# telescope_circuit.net
KiCad netlist of a schematic drawn in EAGLE
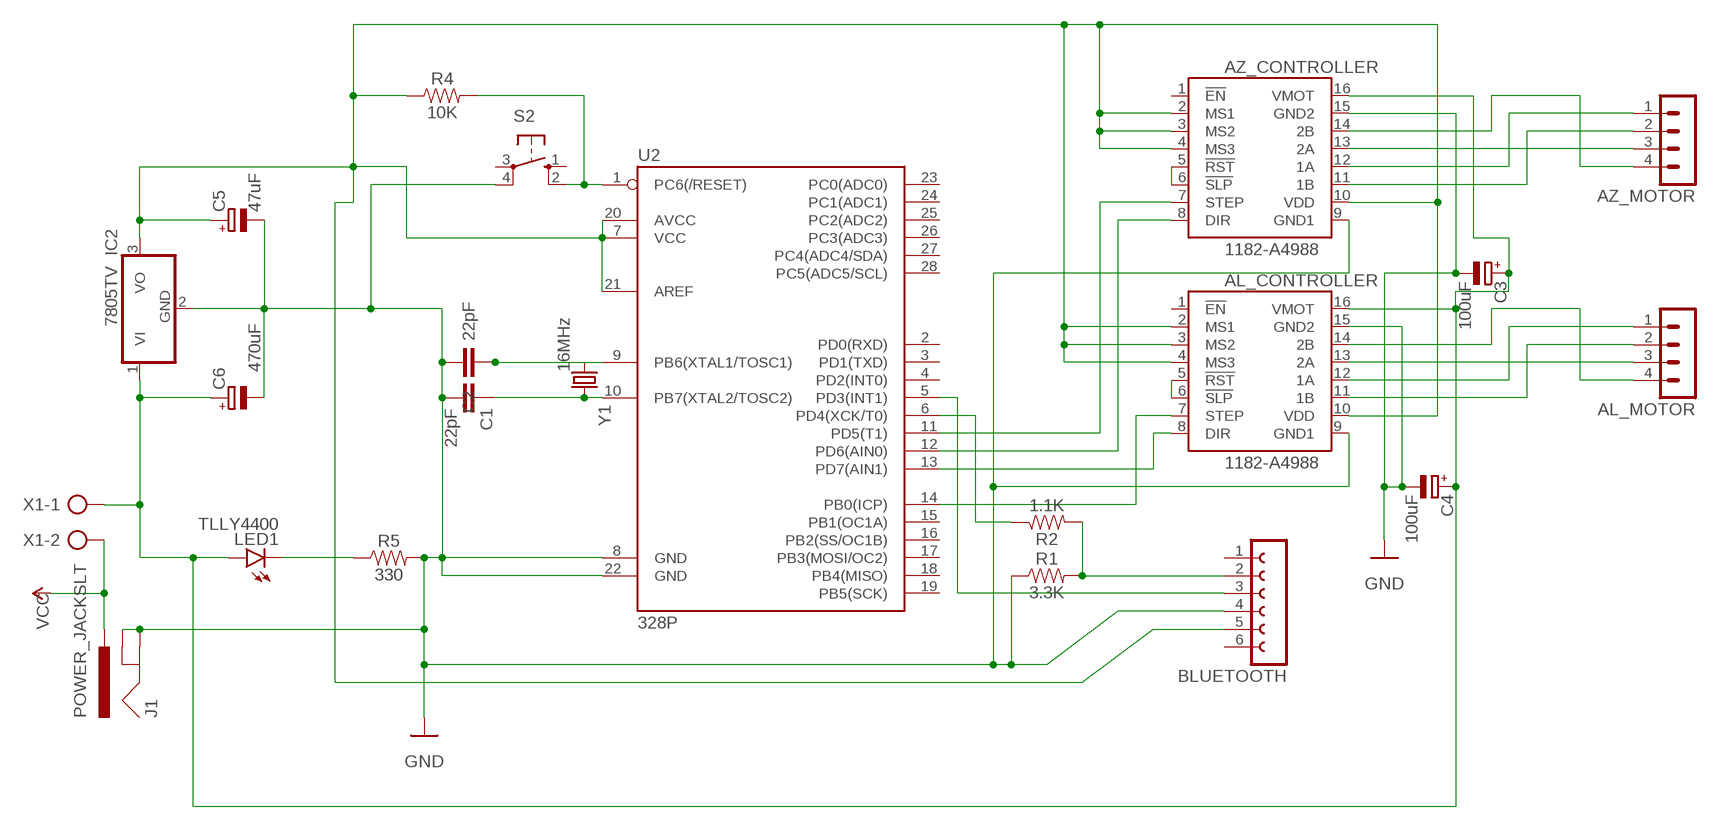
[diagram p0: schematic, sheet 1]

(export (version "E")
  (design (tool "Eeschema 10.0.6"))
  (components
    (comp (ref "AL_CONTROLLER")
      (value "1182-A4988")
      (footprint "eagle-import:A4988")
      (libsource (lib "eagle-import") (part "1182-A4988"))
    )
    (comp (ref "AL_MOTOR")
      (value "MA04-1")
      (footprint "eagle-import:MA04-1")
      (libsource (lib "eagle-import") (part "MA04-1"))
    )
    (comp (ref "AZ_CONTROLLER")
      (value "1182-A4988")
      (footprint "eagle-import:A4988")
      (libsource (lib "eagle-import") (part "1182-A4988"))
    )
    (comp (ref "AZ_MOTOR")
      (value "MA04-1")
      (footprint "eagle-import:MA04-1")
      (libsource (lib "eagle-import") (part "MA04-1"))
    )
    (comp (ref "BLUETOOTH")
      (value "FE06W")
      (footprint "eagle-import:FE06W")
      (libsource (lib "eagle-import") (part "FE06W"))
    )
    (comp (ref "C1")
      (value "22pF")
      (footprint "eagle-import:CAP-PTH-2.54")
      (libsource (lib "eagle-import") (part "22PF-PTH-2.54MM-200V-5%"))
    )
    (comp (ref "C2")
      (value "22pF")
      (footprint "eagle-import:CAP-PTH-2.54")
      (libsource (lib "eagle-import") (part "22PF-PTH-2.54MM-200V-5%"))
    )
    (comp (ref "C3")
      (value "100uF")
      (footprint "eagle-import:E2,5-6")
      (libsource (lib "eagle-import") (part "CPOL-EUE2.5-6"))
    )
    (comp (ref "C4")
      (value "100uF")
      (footprint "eagle-import:E2,5-6")
      (libsource (lib "eagle-import") (part "CPOL-EUE2.5-6"))
    )
    (comp (ref "C5")
      (value "47uF")
      (footprint "eagle-import:E2,5-6")
      (libsource (lib "eagle-import") (part "CPOL-EUE2.5-6"))
    )
    (comp (ref "C6")
      (value "470uF")
      (footprint "eagle-import:E2,5-6")
      (libsource (lib "eagle-import") (part "CPOL-EUE2.5-6"))
    )
    (comp (ref "IC2")
      (value "7805TV")
      (footprint "eagle-import:TO220V")
      (libsource (lib "eagle-import") (part "78TV05"))
    )
    (comp (ref "J1")
      (value "POWER_JACKSLT")
      (footprint "eagle-import:POWER_JACK_SLOT")
      (libsource (lib "eagle-import") (part "POWER_JACKSLT"))
    )
    (comp (ref "LED1")
      (value "TLLY4400")
      (footprint "eagle-import:LED3MM")
      (fields (field (name "MF") "VISHAY SEMICONDUCTOR"))
      (libsource (lib "eagle-import") (part "TLLY4400"))
    )
    (comp (ref "R1")
      (value "3.3K")
      (footprint "eagle-import:AXIAL-0.3")
      (libsource (lib "eagle-import") (part "RESISTORAXIAL-0.3"))
    )
    (comp (ref "R2")
      (value "1.1K")
      (footprint "eagle-import:AXIAL-0.3")
      (libsource (lib "eagle-import") (part "RESISTORAXIAL-0.3"))
    )
    (comp (ref "R4")
      (value "10K")
      (footprint "eagle-import:AXIAL-0.3")
      (libsource (lib "eagle-import") (part "RESISTORAXIAL-0.3"))
    )
    (comp (ref "R5")
      (value "330")
      (footprint "eagle-import:AXIAL-0.3")
      (libsource (lib "eagle-import") (part "RESISTORAXIAL-0.3"))
    )
    (comp (ref "S2")
      (value "10-XX")
      (footprint "eagle-import:B3F-10XX")
      (fields (field (name "MPN") "B3F-1000"))
      (libsource (lib "eagle-import") (part "10-XX"))
    )
    (comp (ref "U2")
      (value "328P")
      (footprint "eagle-import:DIP28")
      (libsource (lib "eagle-import") (part "ATMEGA328P_PDIP"))
    )
    (comp (ref "X1")
      (value "AK500/2")
      (footprint "eagle-import:AK500_2")
      (libsource (lib "eagle-import") (part "AK500/2"))
    )
    (comp (ref "Y1")
      (value "16MHz")
      (footprint "eagle-import:HC49US")
      (libsource (lib "eagle-import") (part "CRYSTAL-16MHZPTH-HC49US"))
    )
  )
  (nets
    (net (code "1") (name "GND") (class "Default")
      (node (ref "AL_CONTROLLER") (pin "15") (pinfunction "GND2_15") (pintype "power_in"))
      (node (ref "AL_CONTROLLER") (pin "9") (pinfunction "GND1_9") (pintype "power_in"))
      (node (ref "AZ_CONTROLLER") (pin "15") (pinfunction "GND2_15") (pintype "power_in"))
      (node (ref "AZ_CONTROLLER") (pin "9") (pinfunction "GND1_9") (pintype "power_in"))
      (node (ref "BLUETOOTH") (pin "4") (pinfunction "4_4") (pintype "passive"))
      (node (ref "C1") (pin "2") (pinfunction "2_2") (pintype "passive"))
      (node (ref "C2") (pin "2") (pinfunction "2_2") (pintype "passive"))
      (node (ref "C3") (pin "-") (pinfunction "-_-") (pintype "passive"))
      (node (ref "C4") (pin "-") (pinfunction "-_-") (pintype "passive"))
      (node (ref "C5") (pin "-") (pinfunction "-_-") (pintype "passive"))
      (node (ref "C6") (pin "-") (pinfunction "-_-") (pintype "passive"))
      (node (ref "IC2") (pin "2") (pinfunction "GND_2") (pintype "passive"))
      (node (ref "J1") (pin "GND@1") (pinfunction "GNDBREAK_GND@1") (pintype "bidirectional"))
      (node (ref "J1") (pin "GND@2") (pinfunction "GND_GND@2") (pintype "bidirectional"))
      (node (ref "R1") (pin "P$1") (pinfunction "1_P$1") (pintype "passive"))
      (node (ref "R5") (pin "P$2") (pinfunction "2_P$2") (pintype "passive"))
      (node (ref "S2") (pin "4") (pinfunction "P1_4") (pintype "passive"))
      (node (ref "U2") (pin "22") (pinfunction "GND_22") (pintype "bidirectional"))
      (node (ref "U2") (pin "8") (pinfunction "GND_8") (pintype "bidirectional"))
    )
    (net (code "2") (name "Net-(AL_CONTROLLER-1A)") (class "Default")
      (node (ref "AL_CONTROLLER") (pin "12") (pinfunction "1A_12") (pintype "output"))
      (node (ref "AL_MOTOR") (pin "1") (pinfunction "1_1") (pintype "passive"))
    )
    (net (code "3") (name "Net-(AL_CONTROLLER-1B)") (class "Default")
      (node (ref "AL_CONTROLLER") (pin "11") (pinfunction "1B_11") (pintype "output"))
      (node (ref "AL_MOTOR") (pin "2") (pinfunction "2_2") (pintype "passive"))
    )
    (net (code "4") (name "Net-(AL_CONTROLLER-2A)") (class "Default")
      (node (ref "AL_CONTROLLER") (pin "13") (pinfunction "2A_13") (pintype "output"))
      (node (ref "AL_MOTOR") (pin "3") (pinfunction "3_3") (pintype "passive"))
    )
    (net (code "5") (name "Net-(AL_CONTROLLER-2B)") (class "Default")
      (node (ref "AL_CONTROLLER") (pin "14") (pinfunction "2B_14") (pintype "output"))
      (node (ref "AL_MOTOR") (pin "4") (pinfunction "4_4") (pintype "passive"))
    )
    (net (code "6") (name "Net-(AL_CONTROLLER-DIR)") (class "Default")
      (node (ref "AL_CONTROLLER") (pin "8") (pinfunction "DIR_8") (pintype "input"))
      (node (ref "U2") (pin "13") (pinfunction "PD7(AIN1)_13") (pintype "bidirectional"))
    )
    (net (code "7") (name "Net-(AL_CONTROLLER-MS1)") (class "Default")
      (node (ref "AL_CONTROLLER") (pin "10") (pinfunction "VDD_10") (pintype "power_in"))
      (node (ref "AL_CONTROLLER") (pin "2") (pinfunction "MS1_2") (pintype "passive"))
      (node (ref "AL_CONTROLLER") (pin "3") (pinfunction "MS2_3") (pintype "passive"))
      (node (ref "AL_CONTROLLER") (pin "4") (pinfunction "MS3_4") (pintype "passive"))
      (node (ref "AZ_CONTROLLER") (pin "10") (pinfunction "VDD_10") (pintype "power_in"))
      (node (ref "AZ_CONTROLLER") (pin "2") (pinfunction "MS1_2") (pintype "passive"))
      (node (ref "AZ_CONTROLLER") (pin "3") (pinfunction "MS2_3") (pintype "passive"))
      (node (ref "AZ_CONTROLLER") (pin "4") (pinfunction "MS3_4") (pintype "passive"))
      (node (ref "BLUETOOTH") (pin "5") (pinfunction "5_5") (pintype "passive"))
      (node (ref "C5") (pin "+") (pinfunction "+_+") (pintype "passive"))
      (node (ref "IC2") (pin "3") (pinfunction "VO_3") (pintype "passive"))
      (node (ref "R4") (pin "P$1") (pinfunction "1_P$1") (pintype "passive"))
      (node (ref "U2") (pin "20") (pinfunction "AVCC_20") (pintype "bidirectional"))
      (node (ref "U2") (pin "21") (pinfunction "AREF_21") (pintype "bidirectional"))
      (node (ref "U2") (pin "7") (pinfunction "VCC_7") (pintype "bidirectional"))
    )
    (net (code "8") (name "Net-(AL_CONTROLLER-STEP)") (class "Default")
      (node (ref "AL_CONTROLLER") (pin "7") (pinfunction "STEP_7") (pintype "input"))
      (node (ref "U2") (pin "14") (pinfunction "PB0(ICP)_14") (pintype "bidirectional"))
    )
    (net (code "9") (name "Net-(AL_CONTROLLER-VMOT)") (class "Default")
      (node (ref "AL_CONTROLLER") (pin "16") (pinfunction "VMOT_16") (pintype "power_in"))
      (node (ref "AZ_CONTROLLER") (pin "16") (pinfunction "VMOT_16") (pintype "power_in"))
      (node (ref "C3") (pin "+") (pinfunction "+_+") (pintype "passive"))
      (node (ref "C4") (pin "+") (pinfunction "+_+") (pintype "passive"))
      (node (ref "C6") (pin "+") (pinfunction "+_+") (pintype "passive"))
      (node (ref "IC2") (pin "1") (pinfunction "VI_1") (pintype "input"))
      (node (ref "LED1") (pin "A") (pinfunction "A_A") (pintype "passive"))
      (node (ref "X1") (pin "1") (pinfunction "KL_1") (pintype "passive"))
    )
    (net (code "10") (name "Net-(AL_CONTROLLER-~{RST})") (class "Default")
      (node (ref "AL_CONTROLLER") (pin "5") (pinfunction "~{RST}_5") (pintype "passive"))
      (node (ref "AL_CONTROLLER") (pin "6") (pinfunction "~{SLP}_6") (pintype "passive"))
    )
    (net (code "11") (name "Net-(AZ_CONTROLLER-1A)") (class "Default")
      (node (ref "AZ_CONTROLLER") (pin "12") (pinfunction "1A_12") (pintype "output"))
      (node (ref "AZ_MOTOR") (pin "1") (pinfunction "1_1") (pintype "passive"))
    )
    (net (code "12") (name "Net-(AZ_CONTROLLER-1B)") (class "Default")
      (node (ref "AZ_CONTROLLER") (pin "11") (pinfunction "1B_11") (pintype "output"))
      (node (ref "AZ_MOTOR") (pin "2") (pinfunction "2_2") (pintype "passive"))
    )
    (net (code "13") (name "Net-(AZ_CONTROLLER-2A)") (class "Default")
      (node (ref "AZ_CONTROLLER") (pin "13") (pinfunction "2A_13") (pintype "output"))
      (node (ref "AZ_MOTOR") (pin "3") (pinfunction "3_3") (pintype "passive"))
    )
    (net (code "14") (name "Net-(AZ_CONTROLLER-2B)") (class "Default")
      (node (ref "AZ_CONTROLLER") (pin "14") (pinfunction "2B_14") (pintype "output"))
      (node (ref "AZ_MOTOR") (pin "4") (pinfunction "4_4") (pintype "passive"))
    )
    (net (code "15") (name "Net-(AZ_CONTROLLER-DIR)") (class "Default")
      (node (ref "AZ_CONTROLLER") (pin "8") (pinfunction "DIR_8") (pintype "input"))
      (node (ref "U2") (pin "12") (pinfunction "PD6(AIN0)_12") (pintype "bidirectional"))
    )
    (net (code "16") (name "Net-(AZ_CONTROLLER-STEP)") (class "Default")
      (node (ref "AZ_CONTROLLER") (pin "7") (pinfunction "STEP_7") (pintype "input"))
      (node (ref "U2") (pin "11") (pinfunction "PD5(T1)_11") (pintype "bidirectional"))
    )
    (net (code "17") (name "Net-(AZ_CONTROLLER-~{RST})") (class "Default")
      (node (ref "AZ_CONTROLLER") (pin "5") (pinfunction "~{RST}_5") (pintype "passive"))
      (node (ref "AZ_CONTROLLER") (pin "6") (pinfunction "~{SLP}_6") (pintype "passive"))
    )
    (net (code "18") (name "Net-(LED1-C)") (class "Default")
      (node (ref "LED1") (pin "K") (pinfunction "C_K") (pintype "passive"))
      (node (ref "R5") (pin "P$1") (pinfunction "1_P$1") (pintype "passive"))
    )
    (net (code "19") (name "Net-(R1-2)") (class "Default")
      (node (ref "BLUETOOTH") (pin "2") (pinfunction "2_2") (pintype "passive"))
      (node (ref "R1") (pin "P$2") (pinfunction "2_P$2") (pintype "passive"))
      (node (ref "R2") (pin "P$2") (pinfunction "2_P$2") (pintype "passive"))
    )
    (net (code "20") (name "Net-(R2-1)") (class "Default")
      (node (ref "R2") (pin "P$1") (pinfunction "1_P$1") (pintype "passive"))
      (node (ref "U2") (pin "6") (pinfunction "PD4(XCK/T0)_6") (pintype "bidirectional"))
    )
    (net (code "21") (name "Net-(R4-2)") (class "Default")
      (node (ref "R4") (pin "P$2") (pinfunction "2_P$2") (pintype "passive"))
      (node (ref "S2") (pin "2") (pinfunction "S1_2") (pintype "passive"))
      (node (ref "U2") (pin "1") (pinfunction "PC6(/RESET)_1") (pintype "bidirectional"))
    )
    (net (code "22") (name "Net-(U2-PB6(XTAL1{slash}TOSC1))") (class "Default")
      (node (ref "C2") (pin "1") (pinfunction "1_1") (pintype "passive"))
      (node (ref "U2") (pin "9") (pinfunction "PB6(XTAL1/TOSC1)_9") (pintype "bidirectional"))
      (node (ref "Y1") (pin "1") (pinfunction "1_1") (pintype "passive"))
    )
    (net (code "23") (name "Net-(U2-PB7(XTAL2{slash}TOSC2))") (class "Default")
      (node (ref "C1") (pin "1") (pinfunction "1_1") (pintype "passive"))
      (node (ref "U2") (pin "10") (pinfunction "PB7(XTAL2/TOSC2)_10") (pintype "bidirectional"))
      (node (ref "Y1") (pin "2") (pinfunction "2_2") (pintype "passive"))
    )
    (net (code "24") (name "Net-(U2-PD3(INT1))") (class "Default")
      (node (ref "BLUETOOTH") (pin "3") (pinfunction "3_3") (pintype "passive"))
      (node (ref "U2") (pin "5") (pinfunction "PD3(INT1)_5") (pintype "bidirectional"))
    )
    (net (code "25") (name "VCC") (class "Default")
      (node (ref "J1") (pin "PWR") (pinfunction "PWR_PWR") (pintype "bidirectional"))
      (node (ref "X1") (pin "2") (pinfunction "KL_2") (pintype "passive"))
    )
    (net (code "26") (name "unconnected-(AL_CONTROLLER-~{EN}-Pad1)") (class "Default")
      (node (ref "AL_CONTROLLER") (pin "1") (pinfunction "~{EN}_1") (pintype "passive"))
    )
    (net (code "27") (name "unconnected-(AZ_CONTROLLER-~{EN}-Pad1)") (class "Default")
      (node (ref "AZ_CONTROLLER") (pin "1") (pinfunction "~{EN}_1") (pintype "passive"))
    )
    (net (code "28") (name "unconnected-(BLUETOOTH-Pad1)") (class "Default")
      (node (ref "BLUETOOTH") (pin "1") (pinfunction "1_1") (pintype "passive"))
    )
    (net (code "29") (name "unconnected-(BLUETOOTH-Pad6)") (class "Default")
      (node (ref "BLUETOOTH") (pin "6") (pinfunction "6_6") (pintype "passive"))
    )
    (net (code "30") (name "unconnected-(S2-P-Pad3)") (class "Default")
      (node (ref "S2") (pin "3") (pinfunction "P_3") (pintype "passive"))
    )
    (net (code "31") (name "unconnected-(S2-S-Pad1)") (class "Default")
      (node (ref "S2") (pin "1") (pinfunction "S_1") (pintype "passive"))
    )
    (net (code "32") (name "unconnected-(U2-PB1(OC1A)-Pad15)") (class "Default")
      (node (ref "U2") (pin "15") (pinfunction "PB1(OC1A)_15") (pintype "bidirectional"))
    )
    (net (code "33") (name "unconnected-(U2-PB2(SS{slash}OC1B)-Pad16)") (class "Default")
      (node (ref "U2") (pin "16") (pinfunction "PB2(SS/OC1B)_16") (pintype "bidirectional"))
    )
    (net (code "34") (name "unconnected-(U2-PB3(MOSI{slash}OC2)-Pad17)") (class "Default")
      (node (ref "U2") (pin "17") (pinfunction "PB3(MOSI/OC2)_17") (pintype "bidirectional"))
    )
    (net (code "35") (name "unconnected-(U2-PB4(MISO)-Pad18)") (class "Default")
      (node (ref "U2") (pin "18") (pinfunction "PB4(MISO)_18") (pintype "bidirectional"))
    )
    (net (code "36") (name "unconnected-(U2-PB5(SCK)-Pad19)") (class "Default")
      (node (ref "U2") (pin "19") (pinfunction "PB5(SCK)_19") (pintype "bidirectional"))
    )
    (net (code "37") (name "unconnected-(U2-PC0(ADC0)-Pad23)") (class "Default")
      (node (ref "U2") (pin "23") (pinfunction "PC0(ADC0)_23") (pintype "bidirectional"))
    )
    (net (code "38") (name "unconnected-(U2-PC1(ADC1)-Pad24)") (class "Default")
      (node (ref "U2") (pin "24") (pinfunction "PC1(ADC1)_24") (pintype "bidirectional"))
    )
    (net (code "39") (name "unconnected-(U2-PC2(ADC2)-Pad25)") (class "Default")
      (node (ref "U2") (pin "25") (pinfunction "PC2(ADC2)_25") (pintype "bidirectional"))
    )
    (net (code "40") (name "unconnected-(U2-PC3(ADC3)-Pad26)") (class "Default")
      (node (ref "U2") (pin "26") (pinfunction "PC3(ADC3)_26") (pintype "bidirectional"))
    )
    (net (code "41") (name "unconnected-(U2-PC4(ADC4{slash}SDA)-Pad27)") (class "Default")
      (node (ref "U2") (pin "27") (pinfunction "PC4(ADC4/SDA)_27") (pintype "bidirectional"))
    )
    (net (code "42") (name "unconnected-(U2-PC5(ADC5{slash}SCL)-Pad28)") (class "Default")
      (node (ref "U2") (pin "28") (pinfunction "PC5(ADC5/SCL)_28") (pintype "bidirectional"))
    )
    (net (code "43") (name "unconnected-(U2-PD0(RXD)-Pad2)") (class "Default")
      (node (ref "U2") (pin "2") (pinfunction "PD0(RXD)_2") (pintype "bidirectional"))
    )
    (net (code "44") (name "unconnected-(U2-PD1(TXD)-Pad3)") (class "Default")
      (node (ref "U2") (pin "3") (pinfunction "PD1(TXD)_3") (pintype "bidirectional"))
    )
    (net (code "45") (name "unconnected-(U2-PD2(INT0)-Pad4)") (class "Default")
      (node (ref "U2") (pin "4") (pinfunction "PD2(INT0)_4") (pintype "bidirectional"))
    )
  )
)
